# PLWD_LTE_Power.net
KiCad netlist of a schematic drawn in Altium Designer
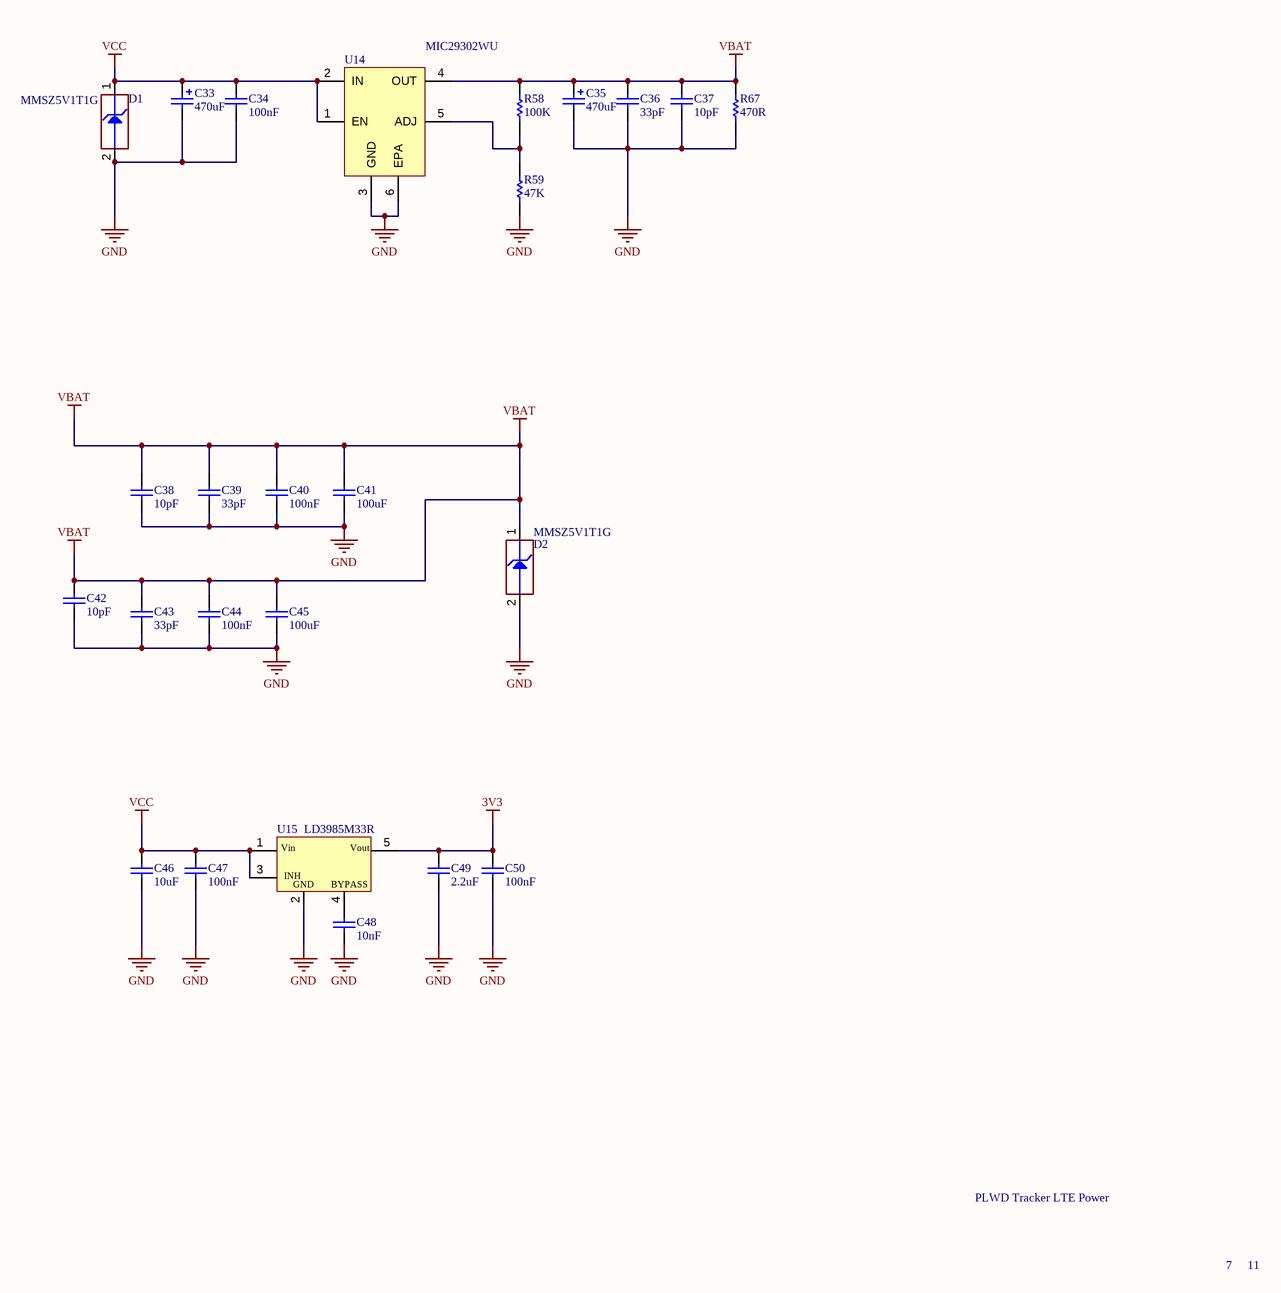
[diagram p0: PLWD_LTE_Power.SchDoc]

(export (version "E")
  (design (tool "Eeschema 10.0.6"))
  (components
    (comp (ref "C33")
      (value "470uF")
      (footprint "CPOL_SANIO_TPB-D4_H380")
      (description "capacitor 470uF 6,3V 20% SANYO")
      (fields
        (field (name "INTERNAL_PART_NUMBER") "MCD-00278")
        (field (name "MANUFACTURER_PART_NUMBER") "6TPB470M")
        (field (name "PROVIDED_BY") "Subcon")
      )
      (libsource (lib "MCD_PARTS_database") (part "Cap_POL_TANA"))
    )
    (comp (ref "C34")
      (value "100nF")
      (footprint "C0402")
      (description "Capacitor,100nF,16V,X7R,10%,0402,YAGEO")
      (fields
        (field (name "INTERNAL_PART_NUMBER") "MCD-00006")
        (field (name "MANUFACTURER_PART_NUMBER") "CC0402KRX7R7BB104")
        (field (name "PROVIDED_BY") "Subcon")
      )
      (libsource (lib "MCD_PARTS_database") (part "Capacitor"))
    )
    (comp (ref "C35")
      (value "470uF")
      (footprint "CPOL_SANIO_TPB-D4_H380")
      (description "capacitor 470uF 6,3V 20% SANYO")
      (fields
        (field (name "INTERNAL_PART_NUMBER") "MCD-00278")
        (field (name "MANUFACTURER_PART_NUMBER") "6TPB470M")
        (field (name "PROVIDED_BY") "Subcon")
      )
      (libsource (lib "MCD_PARTS_database") (part "Cap_POL_TANA"))
    )
    (comp (ref "C36")
      (value "33pF")
      (footprint "C0402")
      (description "capacitor 33pF 50V 5% 0402 COG YAGEO")
      (fields
        (field (name "INTERNAL_PART_NUMBER") "MCD-00277")
        (field (name "MANUFACTURER_PART_NUMBER") "CC0402JRNPO9BN330")
        (field (name "PROVIDED_BY") "Subcon")
      )
      (libsource (lib "MCD_PARTS_database") (part "Capacitor"))
    )
    (comp (ref "C37")
      (value "10pF")
      (footprint "C0402")
      (description "Capacitor,10pF,50V,NPO,5%,0402,YAGEO")
      (fields
        (field (name "INTERNAL_PART_NUMBER") "MCD-00015")
        (field (name "MANUFACTURER_PART_NUMBER") "CC0402JRNPO9BN100")
        (field (name "PROVIDED_BY") "subcon")
      )
      (libsource (lib "MCD_PARTS_database") (part "Capacitor"))
    )
    (comp (ref "C38")
      (value "10pF")
      (footprint "C0402")
      (description "Capacitor,10pF,50V,NPO,5%,0402,YAGEO")
      (fields
        (field (name "INTERNAL_PART_NUMBER") "MCD-00015")
        (field (name "MANUFACTURER_PART_NUMBER") "CC0402JRNPO9BN100")
        (field (name "PROVIDED_BY") "subcon")
      )
      (libsource (lib "MCD_PARTS_database") (part "Capacitor"))
    )
    (comp (ref "C39")
      (value "33pF")
      (footprint "C0402")
      (description "capacitor 33pF 50V 5% 0402 COG YAGEO")
      (fields
        (field (name "INTERNAL_PART_NUMBER") "MCD-00277")
        (field (name "MANUFACTURER_PART_NUMBER") "CC0402JRNPO9BN330")
        (field (name "PROVIDED_BY") "Subcon")
      )
      (libsource (lib "MCD_PARTS_database") (part "Capacitor"))
    )
    (comp (ref "C40")
      (value "100nF")
      (footprint "C0402")
      (description "Capacitor,100nF,16V,X7R,10%,0402,YAGEO")
      (fields
        (field (name "INTERNAL_PART_NUMBER") "MCD-00006")
        (field (name "MANUFACTURER_PART_NUMBER") "CC0402KRX7R7BB104")
        (field (name "PROVIDED_BY") "Subcon")
      )
      (libsource (lib "MCD_PARTS_database") (part "Capacitor"))
    )
    (comp (ref "C41")
      (value "100uF")
      (footprint "C1210")
      (description "Capacitor,100uF,6V3,X5R,10%,1210")
      (fields
        (field (name "INTERNAL_PART_NUMBER") "MCD-00103")
        (field (name "MANUFACTURER_PART_NUMBER") "12106D107KAT2A")
      )
      (libsource (lib "MCD_PARTS_database") (part "Capacitor"))
    )
    (comp (ref "C42")
      (value "10pF")
      (footprint "C0402")
      (description "Capacitor,10pF,50V,NPO,5%,0402,YAGEO")
      (fields
        (field (name "INTERNAL_PART_NUMBER") "MCD-00015")
        (field (name "MANUFACTURER_PART_NUMBER") "CC0402JRNPO9BN100")
        (field (name "PROVIDED_BY") "subcon")
      )
      (libsource (lib "MCD_PARTS_database") (part "Capacitor"))
    )
    (comp (ref "C43")
      (value "33pF")
      (footprint "C0402")
      (description "capacitor 33pF 50V 5% 0402 COG YAGEO")
      (fields
        (field (name "INTERNAL_PART_NUMBER") "MCD-00277")
        (field (name "MANUFACTURER_PART_NUMBER") "CC0402JRNPO9BN330")
        (field (name "PROVIDED_BY") "Subcon")
      )
      (libsource (lib "MCD_PARTS_database") (part "Capacitor"))
    )
    (comp (ref "C44")
      (value "100nF")
      (footprint "C0402")
      (description "Capacitor,100nF,16V,X7R,10%,0402,YAGEO")
      (fields
        (field (name "INTERNAL_PART_NUMBER") "MCD-00006")
        (field (name "MANUFACTURER_PART_NUMBER") "CC0402KRX7R7BB104")
        (field (name "PROVIDED_BY") "Subcon")
      )
      (libsource (lib "MCD_PARTS_database") (part "Capacitor"))
    )
    (comp (ref "C45")
      (value "100uF")
      (footprint "C1210")
      (description "Capacitor,100uF,6V3,X5R,10%,1210")
      (fields
        (field (name "INTERNAL_PART_NUMBER") "MCD-00103")
        (field (name "MANUFACTURER_PART_NUMBER") "12106D107KAT2A")
      )
      (libsource (lib "MCD_PARTS_database") (part "Capacitor"))
    )
    (comp (ref "C46")
      (value "10uF")
      (footprint "C0603")
      (description "Capacitor,10uF,6V3,X5R,10%,0603,YAGEO")
      (fields
        (field (name "INTERNAL_PART_NUMBER") "MCD-00243")
        (field (name "MANUFACTURER_PART_NUMBER") "CC0603KRX5R5BB106")
        (field (name "PROVIDED_BY") "Subcon")
      )
      (libsource (lib "MCD_PARTS_database") (part "Capacitor"))
    )
    (comp (ref "C47")
      (value "100nF")
      (footprint "C0402")
      (description "Capacitor,100nF,16V,X7R,10%,0402,YAGEO")
      (fields
        (field (name "INTERNAL_PART_NUMBER") "MCD-00006")
        (field (name "MANUFACTURER_PART_NUMBER") "CC0402KRX7R7BB104")
        (field (name "PROVIDED_BY") "Subcon")
      )
      (libsource (lib "MCD_PARTS_database") (part "Capacitor"))
    )
    (comp (ref "C48")
      (value "10nF")
      (footprint "C0402")
      (description "Capacitor,10nF,16V,X7R,10%,0402,YAGEO")
      (fields
        (field (name "INTERNAL_PART_NUMBER") "MCD-00011")
        (field (name "MANUFACTURER_PART_NUMBER") "CC0402KRX7R7BB103")
        (field (name "PROVIDED_BY") "Subcon")
      )
      (libsource (lib "MCD_PARTS_database") (part "Capacitor"))
    )
    (comp (ref "C49")
      (value "2.2uF")
      (footprint "C0603")
      (description "Capacitor,2.2uF,10V, X5R,10%,0603,YAGEO")
      (fields
        (field (name "INTERNAL_PART_NUMBER") "MCD-00012")
        (field (name "MANUFACTURER_PART_NUMBER") "CC0603KRX5R6BB225")
        (field (name "PROVIDED_BY") "Subcon")
      )
      (libsource (lib "MCD_PARTS_database") (part "Capacitor"))
    )
    (comp (ref "C50")
      (value "100nF")
      (footprint "C0402")
      (description "Capacitor,100nF,16V,X7R,10%,0402,YAGEO")
      (fields
        (field (name "INTERNAL_PART_NUMBER") "MCD-00006")
        (field (name "MANUFACTURER_PART_NUMBER") "CC0402KRX7R7BB104")
        (field (name "PROVIDED_BY") "Subcon")
      )
      (libsource (lib "MCD_PARTS_database") (part "Capacitor"))
    )
    (comp (ref "D1")
      (value "MMSZ5V1T1G")
      (footprint "DIOZ_SOD123_1K_2A")
      (description "Diode zener")
      (fields
        (field (name "INTERNAL_PART_NUMBER") "MCD-00330")
        (field (name "MANUFACTURER") "Onsemi")
        (field (name "PROVIDED_BY") "Subcon")
      )
      (libsource (lib "MCD_PARTS_database") (part "MMSZ5V1T1G"))
    )
    (comp (ref "D2")
      (value "MMSZ5V1T1G")
      (footprint "DIOZ_SOD123_1K_2A")
      (description "Diode zener")
      (fields
        (field (name "INTERNAL_PART_NUMBER") "MCD-00330")
        (field (name "MANUFACTURER") "Onsemi")
        (field (name "PROVIDED_BY") "Subcon")
      )
      (libsource (lib "MCD_PARTS_database") (part "MMSZ5V1T1G"))
    )
    (comp (ref "R58")
      (value "100K")
      (footprint "R0402")
      (description "Resistor,100K,0402,1%,YAGEO")
      (fields
        (field (name "INTERNAL_PART_NUMBER") "MCD-00059")
        (field (name "MANUFACTURER_PART_NUMBER") "RC0402FR-07100KL")
        (field (name "PROVIDED_BY") "Subcon")
      )
      (libsource (lib "MCD_PARTS_database") (part "Resistor"))
    )
    (comp (ref "R59")
      (value "47K")
      (footprint "R0402")
      (description "Resistor,47K,0402,1%,YAGEO")
      (fields
        (field (name "INTERNAL_PART_NUMBER") "MCD-00063")
        (field (name "MANUFACTURER_PART_NUMBER") "RC0402FR-0747KL")
        (field (name "PROVIDED_BY") "Subcon")
      )
      (libsource (lib "MCD_PARTS_database") (part "Resistor"))
    )
    (comp (ref "R67")
      (value "470R")
      (footprint "R0402")
      (description "Resistor,470R,0402,1%,YAGEO")
      (fields
        (field (name "INTERNAL_PART_NUMBER") "MCD-00178")
        (field (name "MANUFACTURER_PART_NUMBER") "RC0402FR-07470RL")
        (field (name "PROVIDED_BY") "Subcon")
      )
      (libsource (lib "MCD_PARTS_database") (part "Resistor"))
    )
    (comp (ref "U14")
      (value "MIC29302WU")
      (footprint "LDO_TO263-5L-EPAD_D2PAK_P170")
      (description "LDO Ajustable, VOUT=1V25-to-25V,3A,VINmax=26V")
      (fields
        (field (name "INTERNAL_PART_NUMBER") "MCD-00283")
        (field (name "MANUFACTURER") "MICREL")
        (field (name "PROVIDED_BY") "Subcon")
      )
      (libsource (lib "MCD_PARTS_database") (part "MIC29302WU"))
    )
    (comp (ref "U15")
      (value "LD3985M33R")
      (footprint "REG_SOT23-5L")
      (description "Ultra low drop-low noise BiCMOS voltage, regulators low ESR capacitors compatible")
      (fields
        (field (name "INTERNAL_PART_NUMBER") "MCD-00086")
        (field (name "MANUFACTURER") "STM")
        (field (name "PROVIDED_BY") "STM")
      )
      (libsource (lib "MCD_PARTS_database") (part "LD3985M33R"))
    )
  )
  (nets
    (net (code "1") (name "3V3") (class "Default")
      (node (ref "C49") (pin "2") (pinfunction "2_2") (pintype "passive"))
      (node (ref "C50") (pin "2") (pinfunction "2_2") (pintype "passive"))
      (node (ref "U15") (pin "5") (pinfunction "Vout_5") (pintype "passive"))
    )
    (net (code "2") (name "GND") (class "Default")
      (node (ref "C33") (pin "2") (pinfunction "2_2") (pintype "passive"))
      (node (ref "C34") (pin "2") (pinfunction "2_2") (pintype "passive"))
      (node (ref "C35") (pin "2") (pinfunction "2_2") (pintype "passive"))
      (node (ref "C36") (pin "1") (pinfunction "1_1") (pintype "passive"))
      (node (ref "C37") (pin "1") (pinfunction "1_1") (pintype "passive"))
      (node (ref "C38") (pin "1") (pinfunction "1_1") (pintype "passive"))
      (node (ref "C39") (pin "1") (pinfunction "1_1") (pintype "passive"))
      (node (ref "C40") (pin "2") (pinfunction "2_2") (pintype "passive"))
      (node (ref "C41") (pin "1") (pinfunction "1_1") (pintype "passive"))
      (node (ref "C42") (pin "1") (pinfunction "1_1") (pintype "passive"))
      (node (ref "C43") (pin "1") (pinfunction "1_1") (pintype "passive"))
      (node (ref "C44") (pin "2") (pinfunction "2_2") (pintype "passive"))
      (node (ref "C45") (pin "1") (pinfunction "1_1") (pintype "passive"))
      (node (ref "C46") (pin "1") (pinfunction "1_1") (pintype "passive"))
      (node (ref "C47") (pin "1") (pinfunction "1_1") (pintype "passive"))
      (node (ref "C48") (pin "2") (pinfunction "2_2") (pintype "passive"))
      (node (ref "C49") (pin "1") (pinfunction "1_1") (pintype "passive"))
      (node (ref "C50") (pin "1") (pinfunction "1_1") (pintype "passive"))
      (node (ref "D1") (pin "2") (pinfunction "A_2") (pintype "passive"))
      (node (ref "D2") (pin "2") (pinfunction "A_2") (pintype "passive"))
      (node (ref "R59") (pin "1") (pinfunction "1_1") (pintype "passive"))
      (node (ref "R67") (pin "1") (pinfunction "1_1") (pintype "passive"))
      (node (ref "U14") (pin "3") (pinfunction "GND_3") (pintype "passive"))
      (node (ref "U14") (pin "6") (pinfunction "EPA_6") (pintype "passive"))
      (node (ref "U15") (pin "2") (pinfunction "GND_2") (pintype "passive"))
    )
    (net (code "3") (name "Net-(U14-ADJ)") (class "Default")
      (node (ref "R58") (pin "1") (pinfunction "1_1") (pintype "passive"))
      (node (ref "R59") (pin "2") (pinfunction "2_2") (pintype "passive"))
      (node (ref "U14") (pin "5") (pinfunction "ADJ_5") (pintype "passive"))
    )
    (net (code "4") (name "Net-(U15-BYPASS)") (class "Default")
      (node (ref "C48") (pin "1") (pinfunction "1_1") (pintype "passive"))
      (node (ref "U15") (pin "4") (pinfunction "BYPASS_4") (pintype "passive"))
    )
    (net (code "5") (name "VBAT") (class "Default")
      (node (ref "C35") (pin "1") (pinfunction "1_1") (pintype "passive"))
      (node (ref "C36") (pin "2") (pinfunction "2_2") (pintype "passive"))
      (node (ref "C37") (pin "2") (pinfunction "2_2") (pintype "passive"))
      (node (ref "C38") (pin "2") (pinfunction "2_2") (pintype "passive"))
      (node (ref "C39") (pin "2") (pinfunction "2_2") (pintype "passive"))
      (node (ref "C40") (pin "1") (pinfunction "1_1") (pintype "passive"))
      (node (ref "C41") (pin "2") (pinfunction "2_2") (pintype "passive"))
      (node (ref "C42") (pin "2") (pinfunction "2_2") (pintype "passive"))
      (node (ref "C43") (pin "2") (pinfunction "2_2") (pintype "passive"))
      (node (ref "C44") (pin "1") (pinfunction "1_1") (pintype "passive"))
      (node (ref "C45") (pin "2") (pinfunction "2_2") (pintype "passive"))
      (node (ref "D2") (pin "1") (pinfunction "K_1") (pintype "passive"))
      (node (ref "R58") (pin "2") (pinfunction "2_2") (pintype "passive"))
      (node (ref "R67") (pin "2") (pinfunction "2_2") (pintype "passive"))
      (node (ref "U14") (pin "4") (pinfunction "OUT_4") (pintype "passive"))
    )
    (net (code "6") (name "VCC") (class "Default")
      (node (ref "C33") (pin "1") (pinfunction "1_1") (pintype "passive"))
      (node (ref "C34") (pin "1") (pinfunction "1_1") (pintype "passive"))
      (node (ref "C46") (pin "2") (pinfunction "2_2") (pintype "passive"))
      (node (ref "C47") (pin "2") (pinfunction "2_2") (pintype "passive"))
      (node (ref "D1") (pin "1") (pinfunction "K_1") (pintype "passive"))
      (node (ref "U14") (pin "1") (pinfunction "EN_1") (pintype "passive"))
      (node (ref "U14") (pin "2") (pinfunction "IN_2") (pintype "passive"))
      (node (ref "U15") (pin "1") (pinfunction "Vin_1") (pintype "passive"))
      (node (ref "U15") (pin "3") (pinfunction "CE_3") (pintype "passive"))
    )
  )
)
